# pigtail.net
KiCad netlist of a schematic drawn in EAGLE
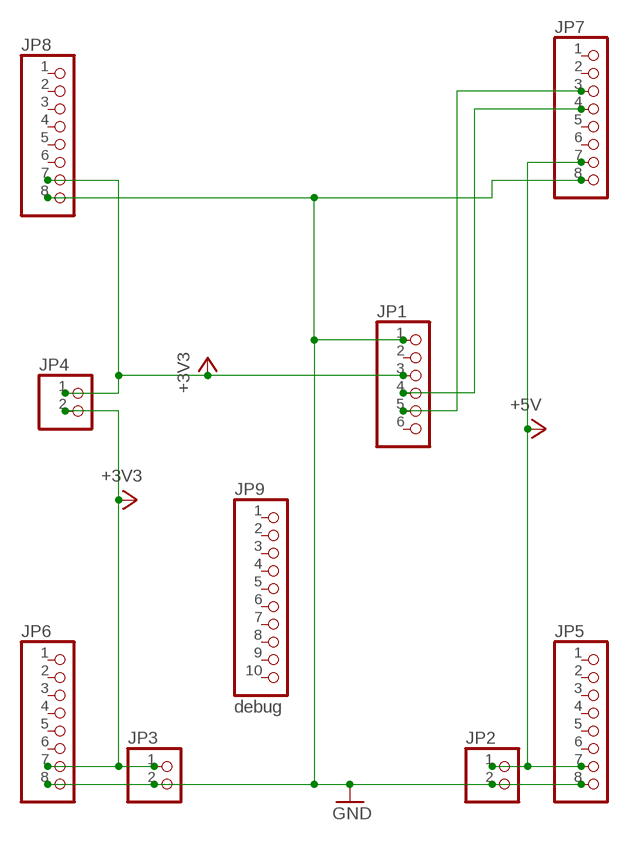
[diagram p0: schematic, sheet 1]

(export (version "E")
  (design (tool "Eeschema 10.0.6"))
  (components
    (comp (ref "JP1")
      (value "PINHD-1X6")
      (footprint "eagle-import:1X06")
      (libsource (lib "eagle-import") (part "PINHD-1X6"))
    )
    (comp (ref "JP2")
      (value "PINHD-1X2")
      (footprint "eagle-import:1X02")
      (libsource (lib "eagle-import") (part "PINHD-1X2"))
    )
    (comp (ref "JP3")
      (value "PINHD-1X2")
      (footprint "eagle-import:1X02")
      (libsource (lib "eagle-import") (part "PINHD-1X2"))
    )
    (comp (ref "JP4")
      (value "PINHD-1X2")
      (footprint "eagle-import:1X02")
      (libsource (lib "eagle-import") (part "PINHD-1X2"))
    )
    (comp (ref "JP5")
      (value "PINHD-1X8")
      (footprint "eagle-import:1X08")
      (libsource (lib "eagle-import") (part "PINHD-1X8"))
    )
    (comp (ref "JP6")
      (value "PINHD-1X8")
      (footprint "eagle-import:1X08")
      (libsource (lib "eagle-import") (part "PINHD-1X8"))
    )
    (comp (ref "JP7")
      (value "PINHD-1X8")
      (footprint "eagle-import:1X08")
      (libsource (lib "eagle-import") (part "PINHD-1X8"))
    )
    (comp (ref "JP8")
      (value "PINHD-1X8")
      (footprint "eagle-import:1X08")
      (libsource (lib "eagle-import") (part "PINHD-1X8"))
    )
    (comp (ref "JP9")
      (value "debug")
      (footprint "eagle-import:1X10")
      (libsource (lib "eagle-import") (part "PINHD-1X10"))
    )
  )
  (nets
    (net (code "1") (name "+3V3") (class "Default")
      (node (ref "JP1") (pin "3") (pinfunction "3_3") (pintype "passive"))
      (node (ref "JP3") (pin "1") (pinfunction "1_1") (pintype "passive"))
      (node (ref "JP4") (pin "1") (pinfunction "1_1") (pintype "passive"))
      (node (ref "JP4") (pin "2") (pinfunction "2_2") (pintype "passive"))
      (node (ref "JP6") (pin "7") (pinfunction "7_7") (pintype "passive"))
      (node (ref "JP8") (pin "7") (pinfunction "7_7") (pintype "passive"))
    )
    (net (code "2") (name "+5V") (class "Default")
      (node (ref "JP2") (pin "1") (pinfunction "1_1") (pintype "passive"))
      (node (ref "JP5") (pin "7") (pinfunction "7_7") (pintype "passive"))
      (node (ref "JP7") (pin "7") (pinfunction "7_7") (pintype "passive"))
    )
    (net (code "3") (name "GND") (class "Default")
      (node (ref "JP1") (pin "1") (pinfunction "1_1") (pintype "passive"))
      (node (ref "JP2") (pin "2") (pinfunction "2_2") (pintype "passive"))
      (node (ref "JP3") (pin "2") (pinfunction "2_2") (pintype "passive"))
      (node (ref "JP5") (pin "8") (pinfunction "8_8") (pintype "passive"))
      (node (ref "JP6") (pin "8") (pinfunction "8_8") (pintype "passive"))
      (node (ref "JP7") (pin "8") (pinfunction "8_8") (pintype "passive"))
      (node (ref "JP8") (pin "8") (pinfunction "8_8") (pintype "passive"))
    )
    (net (code "4") (name "Net-(JP1-Pad4)") (class "Default")
      (node (ref "JP1") (pin "4") (pinfunction "4_4") (pintype "passive"))
      (node (ref "JP7") (pin "4") (pinfunction "4_4") (pintype "passive"))
    )
    (net (code "5") (name "Net-(JP1-Pad5)") (class "Default")
      (node (ref "JP1") (pin "5") (pinfunction "5_5") (pintype "passive"))
      (node (ref "JP7") (pin "3") (pinfunction "3_3") (pintype "passive"))
    )
    (net (code "6") (name "unconnected-(JP1-Pad2)") (class "Default")
      (node (ref "JP1") (pin "2") (pinfunction "2_2") (pintype "passive"))
    )
    (net (code "7") (name "unconnected-(JP1-Pad6)") (class "Default")
      (node (ref "JP1") (pin "6") (pinfunction "6_6") (pintype "passive"))
    )
    (net (code "8") (name "unconnected-(JP5-Pad1)") (class "Default")
      (node (ref "JP5") (pin "1") (pinfunction "1_1") (pintype "passive"))
    )
    (net (code "9") (name "unconnected-(JP5-Pad2)") (class "Default")
      (node (ref "JP5") (pin "2") (pinfunction "2_2") (pintype "passive"))
    )
    (net (code "10") (name "unconnected-(JP5-Pad3)") (class "Default")
      (node (ref "JP5") (pin "3") (pinfunction "3_3") (pintype "passive"))
    )
    (net (code "11") (name "unconnected-(JP5-Pad4)") (class "Default")
      (node (ref "JP5") (pin "4") (pinfunction "4_4") (pintype "passive"))
    )
    (net (code "12") (name "unconnected-(JP5-Pad5)") (class "Default")
      (node (ref "JP5") (pin "5") (pinfunction "5_5") (pintype "passive"))
    )
    (net (code "13") (name "unconnected-(JP5-Pad6)") (class "Default")
      (node (ref "JP5") (pin "6") (pinfunction "6_6") (pintype "passive"))
    )
    (net (code "14") (name "unconnected-(JP6-Pad1)") (class "Default")
      (node (ref "JP6") (pin "1") (pinfunction "1_1") (pintype "passive"))
    )
    (net (code "15") (name "unconnected-(JP6-Pad2)") (class "Default")
      (node (ref "JP6") (pin "2") (pinfunction "2_2") (pintype "passive"))
    )
    (net (code "16") (name "unconnected-(JP6-Pad3)") (class "Default")
      (node (ref "JP6") (pin "3") (pinfunction "3_3") (pintype "passive"))
    )
    (net (code "17") (name "unconnected-(JP6-Pad4)") (class "Default")
      (node (ref "JP6") (pin "4") (pinfunction "4_4") (pintype "passive"))
    )
    (net (code "18") (name "unconnected-(JP6-Pad5)") (class "Default")
      (node (ref "JP6") (pin "5") (pinfunction "5_5") (pintype "passive"))
    )
    (net (code "19") (name "unconnected-(JP6-Pad6)") (class "Default")
      (node (ref "JP6") (pin "6") (pinfunction "6_6") (pintype "passive"))
    )
    (net (code "20") (name "unconnected-(JP7-Pad1)") (class "Default")
      (node (ref "JP7") (pin "1") (pinfunction "1_1") (pintype "passive"))
    )
    (net (code "21") (name "unconnected-(JP7-Pad2)") (class "Default")
      (node (ref "JP7") (pin "2") (pinfunction "2_2") (pintype "passive"))
    )
    (net (code "22") (name "unconnected-(JP7-Pad5)") (class "Default")
      (node (ref "JP7") (pin "5") (pinfunction "5_5") (pintype "passive"))
    )
    (net (code "23") (name "unconnected-(JP7-Pad6)") (class "Default")
      (node (ref "JP7") (pin "6") (pinfunction "6_6") (pintype "passive"))
    )
    (net (code "24") (name "unconnected-(JP8-Pad1)") (class "Default")
      (node (ref "JP8") (pin "1") (pinfunction "1_1") (pintype "passive"))
    )
    (net (code "25") (name "unconnected-(JP8-Pad2)") (class "Default")
      (node (ref "JP8") (pin "2") (pinfunction "2_2") (pintype "passive"))
    )
    (net (code "26") (name "unconnected-(JP8-Pad3)") (class "Default")
      (node (ref "JP8") (pin "3") (pinfunction "3_3") (pintype "passive"))
    )
    (net (code "27") (name "unconnected-(JP8-Pad4)") (class "Default")
      (node (ref "JP8") (pin "4") (pinfunction "4_4") (pintype "passive"))
    )
    (net (code "28") (name "unconnected-(JP8-Pad5)") (class "Default")
      (node (ref "JP8") (pin "5") (pinfunction "5_5") (pintype "passive"))
    )
    (net (code "29") (name "unconnected-(JP8-Pad6)") (class "Default")
      (node (ref "JP8") (pin "6") (pinfunction "6_6") (pintype "passive"))
    )
    (net (code "30") (name "unconnected-(JP9-Pad1)") (class "Default")
      (node (ref "JP9") (pin "1") (pinfunction "1_1") (pintype "passive"))
    )
    (net (code "31") (name "unconnected-(JP9-Pad2)") (class "Default")
      (node (ref "JP9") (pin "2") (pinfunction "2_2") (pintype "passive"))
    )
    (net (code "32") (name "unconnected-(JP9-Pad3)") (class "Default")
      (node (ref "JP9") (pin "3") (pinfunction "3_3") (pintype "passive"))
    )
    (net (code "33") (name "unconnected-(JP9-Pad4)") (class "Default")
      (node (ref "JP9") (pin "4") (pinfunction "4_4") (pintype "passive"))
    )
    (net (code "34") (name "unconnected-(JP9-Pad5)") (class "Default")
      (node (ref "JP9") (pin "5") (pinfunction "5_5") (pintype "passive"))
    )
    (net (code "35") (name "unconnected-(JP9-Pad6)") (class "Default")
      (node (ref "JP9") (pin "6") (pinfunction "6_6") (pintype "passive"))
    )
    (net (code "36") (name "unconnected-(JP9-Pad7)") (class "Default")
      (node (ref "JP9") (pin "7") (pinfunction "7_7") (pintype "passive"))
    )
    (net (code "37") (name "unconnected-(JP9-Pad8)") (class "Default")
      (node (ref "JP9") (pin "8") (pinfunction "8_8") (pintype "passive"))
    )
    (net (code "38") (name "unconnected-(JP9-Pad9)") (class "Default")
      (node (ref "JP9") (pin "9") (pinfunction "9_9") (pintype "passive"))
    )
    (net (code "39") (name "unconnected-(JP9-Pad10)") (class "Default")
      (node (ref "JP9") (pin "10") (pinfunction "10_10") (pintype "passive"))
    )
  )
)
